# power_distribution.net
KiCad netlist of a schematic drawn in EAGLE
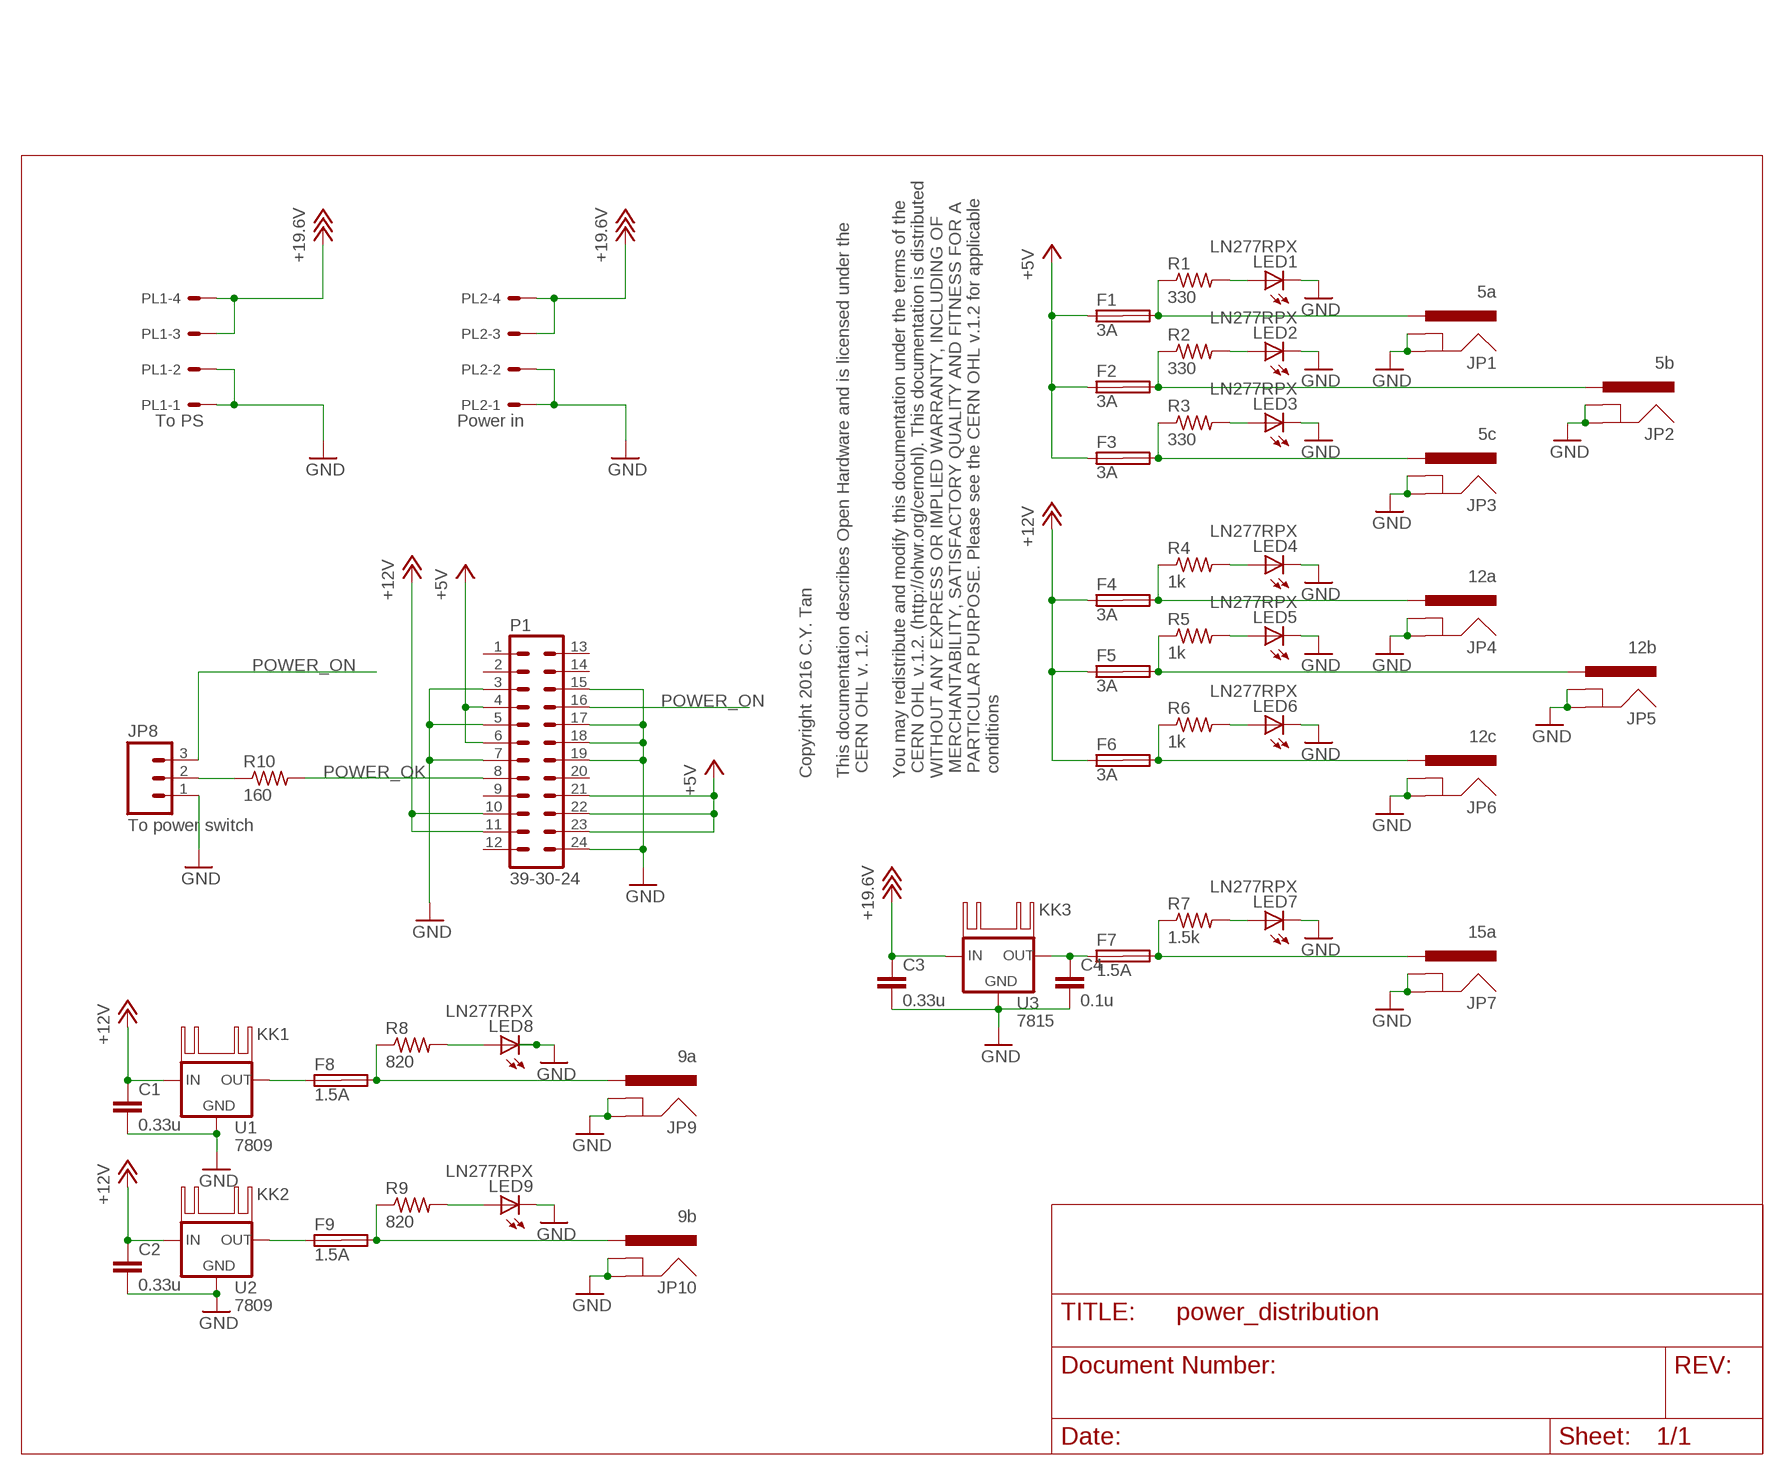
[diagram p0: schematic, sheet 1]

(export (version "E")
  (design (tool "Eeschema 10.0.6"))
  (components
    (comp (ref "C1")
      (value "0.33u")
      (footprint "eagle-import:CAP-PTH-5MM")
      (libsource (lib "eagle-import") (part "CAPPTH1"))
    )
    (comp (ref "C2")
      (value "0.33u")
      (footprint "eagle-import:CAP-PTH-5MM")
      (libsource (lib "eagle-import") (part "CAPPTH1"))
    )
    (comp (ref "C3")
      (value "0.33u")
      (footprint "eagle-import:CAP-PTH-5MM")
      (libsource (lib "eagle-import") (part "CAPPTH1"))
    )
    (comp (ref "C4")
      (value "0.1u")
      (footprint "eagle-import:CAP-PTH-5MM")
      (libsource (lib "eagle-import") (part "CAPPTH1"))
    )
    (comp (ref "F1")
      (value "3A")
      (footprint "eagle-import:SH32")
      (fields (field (name "MPN") "10207101009"))
      (libsource (lib "eagle-import") (part "SH32"))
    )
    (comp (ref "F2")
      (value "3A")
      (footprint "eagle-import:SH32")
      (fields (field (name "MPN") "10207101009"))
      (libsource (lib "eagle-import") (part "SH32"))
    )
    (comp (ref "F3")
      (value "3A")
      (footprint "eagle-import:SH32")
      (fields (field (name "MPN") "10207101009"))
      (libsource (lib "eagle-import") (part "SH32"))
    )
    (comp (ref "F4")
      (value "3A")
      (footprint "eagle-import:SH32")
      (fields (field (name "MPN") "10207101009"))
      (libsource (lib "eagle-import") (part "SH32"))
    )
    (comp (ref "F5")
      (value "3A")
      (footprint "eagle-import:SH32")
      (fields (field (name "MPN") "10207101009"))
      (libsource (lib "eagle-import") (part "SH32"))
    )
    (comp (ref "F6")
      (value "3A")
      (footprint "eagle-import:SH32")
      (fields (field (name "MPN") "10207101009"))
      (libsource (lib "eagle-import") (part "SH32"))
    )
    (comp (ref "F7")
      (value "1.5A")
      (footprint "eagle-import:SH32")
      (fields (field (name "MPN") "10207101009"))
      (libsource (lib "eagle-import") (part "SH32"))
    )
    (comp (ref "F8")
      (value "1.5A")
      (footprint "eagle-import:SH32")
      (fields (field (name "MPN") "10207101009"))
      (libsource (lib "eagle-import") (part "SH32"))
    )
    (comp (ref "F9")
      (value "1.5A")
      (footprint "eagle-import:SH32")
      (fields (field (name "MPN") "10207101009"))
      (libsource (lib "eagle-import") (part "SH32"))
    )
    (comp (ref "JP1")
      (value "5a")
      (footprint "eagle-import:POWER_JACK_V_PTH")
      (libsource (lib "eagle-import") (part "POWER_JACK"))
    )
    (comp (ref "JP2")
      (value "5b")
      (footprint "eagle-import:POWER_JACK_V_PTH")
      (libsource (lib "eagle-import") (part "POWER_JACK"))
    )
    (comp (ref "JP3")
      (value "5c")
      (footprint "eagle-import:POWER_JACK_V_PTH")
      (libsource (lib "eagle-import") (part "POWER_JACK"))
    )
    (comp (ref "JP4")
      (value "12a")
      (footprint "eagle-import:POWER_JACK_V_PTH")
      (libsource (lib "eagle-import") (part "POWER_JACK"))
    )
    (comp (ref "JP5")
      (value "12b")
      (footprint "eagle-import:POWER_JACK_V_PTH")
      (libsource (lib "eagle-import") (part "POWER_JACK"))
    )
    (comp (ref "JP6")
      (value "12c")
      (footprint "eagle-import:POWER_JACK_V_PTH")
      (libsource (lib "eagle-import") (part "POWER_JACK"))
    )
    (comp (ref "JP7")
      (value "15a")
      (footprint "eagle-import:POWER_JACK_V_PTH")
      (libsource (lib "eagle-import") (part "POWER_JACK"))
    )
    (comp (ref "JP8")
      (value "To power switch")
      (footprint "eagle-import:1X03")
      (libsource (lib "eagle-import") (part "M03PTH"))
    )
    (comp (ref "JP9")
      (value "9a")
      (footprint "eagle-import:POWER_JACK_V_PTH")
      (libsource (lib "eagle-import") (part "POWER_JACK"))
    )
    (comp (ref "JP10")
      (value "9b")
      (footprint "eagle-import:POWER_JACK_V_PTH")
      (libsource (lib "eagle-import") (part "POWER_JACK"))
    )
    (comp (ref "KK1")
      (value "TO-220_HEATSINK_4W")
      (footprint "eagle-import:TO-220-HEATSINK-4W")
      (libsource (lib "eagle-import") (part "TO-220_HEATSINK_4W"))
    )
    (comp (ref "KK2")
      (value "TO-220_HEATSINK_4W")
      (footprint "eagle-import:TO-220-HEATSINK-4W")
      (libsource (lib "eagle-import") (part "TO-220_HEATSINK_4W"))
    )
    (comp (ref "KK3")
      (value "TO-220_HEATSINK_4W")
      (footprint "eagle-import:TO-220-HEATSINK-4W")
      (libsource (lib "eagle-import") (part "TO-220_HEATSINK_4W"))
    )
    (comp (ref "LED1")
      (value "LN277RPX")
      (footprint "eagle-import:LED3MM")
      (libsource (lib "eagle-import") (part "LN277RPX"))
    )
    (comp (ref "LED2")
      (value "LN277RPX")
      (footprint "eagle-import:LED3MM")
      (libsource (lib "eagle-import") (part "LN277RPX"))
    )
    (comp (ref "LED3")
      (value "LN277RPX")
      (footprint "eagle-import:LED3MM")
      (libsource (lib "eagle-import") (part "LN277RPX"))
    )
    (comp (ref "LED4")
      (value "LN277RPX")
      (footprint "eagle-import:LED3MM")
      (libsource (lib "eagle-import") (part "LN277RPX"))
    )
    (comp (ref "LED5")
      (value "LN277RPX")
      (footprint "eagle-import:LED3MM")
      (libsource (lib "eagle-import") (part "LN277RPX"))
    )
    (comp (ref "LED6")
      (value "LN277RPX")
      (footprint "eagle-import:LED3MM")
      (libsource (lib "eagle-import") (part "LN277RPX"))
    )
    (comp (ref "LED7")
      (value "LN277RPX")
      (footprint "eagle-import:LED3MM")
      (libsource (lib "eagle-import") (part "LN277RPX"))
    )
    (comp (ref "LED8")
      (value "LN277RPX")
      (footprint "eagle-import:LED3MM")
      (libsource (lib "eagle-import") (part "LN277RPX"))
    )
    (comp (ref "LED9")
      (value "LN277RPX")
      (footprint "eagle-import:LED3MM")
      (libsource (lib "eagle-import") (part "LN277RPX"))
    )
    (comp (ref "P1")
      (value "39-30-24")
      (footprint "eagle-import:39-30-_24_")
      (libsource (lib "eagle-import") (part "39-30-?24?"))
    )
    (comp (ref "PL1")
      (value "To PS")
      (footprint "eagle-import:5569-4")
      (libsource (lib "eagle-import") (part "555X-4H"))
    )
    (comp (ref "PL2")
      (value "Power in")
      (footprint "eagle-import:5569-4")
      (libsource (lib "eagle-import") (part "555X-4H"))
    )
    (comp (ref "R1")
      (value "330")
      (footprint "eagle-import:0207_10")
      (libsource (lib "eagle-import") (part "R-US_0207/10"))
    )
    (comp (ref "R2")
      (value "330")
      (footprint "eagle-import:0207_10")
      (libsource (lib "eagle-import") (part "R-US_0207/10"))
    )
    (comp (ref "R3")
      (value "330")
      (footprint "eagle-import:0207_10")
      (libsource (lib "eagle-import") (part "R-US_0207/10"))
    )
    (comp (ref "R4")
      (value "1k")
      (footprint "eagle-import:0207_10")
      (libsource (lib "eagle-import") (part "R-US_0207/10"))
    )
    (comp (ref "R5")
      (value "1k")
      (footprint "eagle-import:0207_10")
      (libsource (lib "eagle-import") (part "R-US_0207/10"))
    )
    (comp (ref "R6")
      (value "1k")
      (footprint "eagle-import:0207_10")
      (libsource (lib "eagle-import") (part "R-US_0207/10"))
    )
    (comp (ref "R7")
      (value "1.5k")
      (footprint "eagle-import:0207_10")
      (libsource (lib "eagle-import") (part "R-US_0207/10"))
    )
    (comp (ref "R8")
      (value "820")
      (footprint "eagle-import:0207_10")
      (libsource (lib "eagle-import") (part "R-US_0207/10"))
    )
    (comp (ref "R9")
      (value "820")
      (footprint "eagle-import:0207_10")
      (libsource (lib "eagle-import") (part "R-US_0207/10"))
    )
    (comp (ref "R10")
      (value "160")
      (footprint "eagle-import:0207_10")
      (libsource (lib "eagle-import") (part "R-US_0207/10"))
    )
    (comp (ref "U1")
      (value "7809")
      (footprint "eagle-import:TO-220-ALT")
      (libsource (lib "eagle-import") (part "V_REG_78XX-TO-220"))
    )
    (comp (ref "U2")
      (value "7809")
      (footprint "eagle-import:TO-220-ALT")
      (libsource (lib "eagle-import") (part "V_REG_78XX-TO-220"))
    )
    (comp (ref "U3")
      (value "7815")
      (footprint "eagle-import:TO-220-ALT")
      (libsource (lib "eagle-import") (part "V_REG_78XX-TO-220"))
    )
  )
  (nets
    (net (code "1") (name "+5V") (class "Default")
      (node (ref "F1") (pin "1A") (pinfunction "1A_1A") (pintype "passive"))
      (node (ref "F2") (pin "1A") (pinfunction "1A_1A") (pintype "passive"))
      (node (ref "F3") (pin "1A") (pinfunction "1A_1A") (pintype "passive"))
      (node (ref "P1") (pin "21") (pinfunction "21_21") (pintype "passive"))
      (node (ref "P1") (pin "22") (pinfunction "22_22") (pintype "passive"))
      (node (ref "P1") (pin "23") (pinfunction "23_23") (pintype "passive"))
      (node (ref "P1") (pin "4") (pinfunction "4_4") (pintype "passive"))
      (node (ref "P1") (pin "6") (pinfunction "6_6") (pintype "passive"))
    )
    (net (code "2") (name "+12V") (class "Default")
      (node (ref "C1") (pin "1") (pinfunction "1_1") (pintype "passive"))
      (node (ref "C2") (pin "1") (pinfunction "1_1") (pintype "passive"))
      (node (ref "F4") (pin "1A") (pinfunction "1A_1A") (pintype "passive"))
      (node (ref "F5") (pin "1A") (pinfunction "1A_1A") (pintype "passive"))
      (node (ref "F6") (pin "1A") (pinfunction "1A_1A") (pintype "passive"))
      (node (ref "P1") (pin "10") (pinfunction "10_10") (pintype "passive"))
      (node (ref "P1") (pin "11") (pinfunction "11_11") (pintype "passive"))
      (node (ref "U1") (pin "IN") (pinfunction "IN_IN") (pintype "input"))
      (node (ref "U2") (pin "IN") (pinfunction "IN_IN") (pintype "input"))
    )
    (net (code "3") (name "+19.6V") (class "Default")
      (node (ref "C3") (pin "1") (pinfunction "1_1") (pintype "passive"))
      (node (ref "PL1") (pin "3") (pinfunction "S_3") (pintype "passive"))
      (node (ref "PL1") (pin "4") (pinfunction "S_4") (pintype "passive"))
      (node (ref "PL2") (pin "3") (pinfunction "S_3") (pintype "passive"))
      (node (ref "PL2") (pin "4") (pinfunction "S_4") (pintype "passive"))
      (node (ref "U3") (pin "IN") (pinfunction "IN_IN") (pintype "input"))
    )
    (net (code "4") (name "/POWER_OK") (class "Default")
      (node (ref "P1") (pin "8") (pinfunction "8_8") (pintype "passive"))
      (node (ref "R10") (pin "2") (pinfunction "2_2") (pintype "passive"))
    )
    (net (code "5") (name "/POWER_ON") (class "Default")
      (node (ref "JP8") (pin "3") (pinfunction "3_3") (pintype "passive"))
      (node (ref "P1") (pin "16") (pinfunction "16_16") (pintype "passive"))
    )
    (net (code "6") (name "GND") (class "Default")
      (node (ref "C1") (pin "2") (pinfunction "2_2") (pintype "passive"))
      (node (ref "C2") (pin "2") (pinfunction "2_2") (pintype "passive"))
      (node (ref "C3") (pin "2") (pinfunction "2_2") (pintype "passive"))
      (node (ref "C4") (pin "2") (pinfunction "2_2") (pintype "passive"))
      (node (ref "JP1") (pin "GND") (pinfunction "GND_GND") (pintype "bidirectional"))
      (node (ref "JP1") (pin "GNDBREAK") (pinfunction "GNDBREAK_GNDBREAK") (pintype "bidirectional"))
      (node (ref "JP10") (pin "GND") (pinfunction "GND_GND") (pintype "bidirectional"))
      (node (ref "JP10") (pin "GNDBREAK") (pinfunction "GNDBREAK_GNDBREAK") (pintype "bidirectional"))
      (node (ref "JP2") (pin "GND") (pinfunction "GND_GND") (pintype "bidirectional"))
      (node (ref "JP2") (pin "GNDBREAK") (pinfunction "GNDBREAK_GNDBREAK") (pintype "bidirectional"))
      (node (ref "JP3") (pin "GND") (pinfunction "GND_GND") (pintype "bidirectional"))
      (node (ref "JP3") (pin "GNDBREAK") (pinfunction "GNDBREAK_GNDBREAK") (pintype "bidirectional"))
      (node (ref "JP4") (pin "GND") (pinfunction "GND_GND") (pintype "bidirectional"))
      (node (ref "JP4") (pin "GNDBREAK") (pinfunction "GNDBREAK_GNDBREAK") (pintype "bidirectional"))
      (node (ref "JP5") (pin "GND") (pinfunction "GND_GND") (pintype "bidirectional"))
      (node (ref "JP5") (pin "GNDBREAK") (pinfunction "GNDBREAK_GNDBREAK") (pintype "bidirectional"))
      (node (ref "JP6") (pin "GND") (pinfunction "GND_GND") (pintype "bidirectional"))
      (node (ref "JP6") (pin "GNDBREAK") (pinfunction "GNDBREAK_GNDBREAK") (pintype "bidirectional"))
      (node (ref "JP7") (pin "GND") (pinfunction "GND_GND") (pintype "bidirectional"))
      (node (ref "JP7") (pin "GNDBREAK") (pinfunction "GNDBREAK_GNDBREAK") (pintype "bidirectional"))
      (node (ref "JP8") (pin "1") (pinfunction "1_1") (pintype "passive"))
      (node (ref "JP9") (pin "GND") (pinfunction "GND_GND") (pintype "bidirectional"))
      (node (ref "JP9") (pin "GNDBREAK") (pinfunction "GNDBREAK_GNDBREAK") (pintype "bidirectional"))
      (node (ref "LED1") (pin "K") (pinfunction "C_K") (pintype "passive"))
      (node (ref "LED2") (pin "K") (pinfunction "C_K") (pintype "passive"))
      (node (ref "LED3") (pin "K") (pinfunction "C_K") (pintype "passive"))
      (node (ref "LED4") (pin "K") (pinfunction "C_K") (pintype "passive"))
      (node (ref "LED5") (pin "K") (pinfunction "C_K") (pintype "passive"))
      (node (ref "LED6") (pin "K") (pinfunction "C_K") (pintype "passive"))
      (node (ref "LED7") (pin "K") (pinfunction "C_K") (pintype "passive"))
      (node (ref "LED8") (pin "K") (pinfunction "C_K") (pintype "passive"))
      (node (ref "LED9") (pin "K") (pinfunction "C_K") (pintype "passive"))
      (node (ref "P1") (pin "15") (pinfunction "15_15") (pintype "passive"))
      (node (ref "P1") (pin "17") (pinfunction "17_17") (pintype "passive"))
      (node (ref "P1") (pin "18") (pinfunction "18_18") (pintype "passive"))
      (node (ref "P1") (pin "19") (pinfunction "19_19") (pintype "passive"))
      (node (ref "P1") (pin "24") (pinfunction "24_24") (pintype "passive"))
      (node (ref "P1") (pin "3") (pinfunction "3_3") (pintype "passive"))
      (node (ref "P1") (pin "5") (pinfunction "5_5") (pintype "passive"))
      (node (ref "P1") (pin "7") (pinfunction "7_7") (pintype "passive"))
      (node (ref "PL1") (pin "1") (pinfunction "S_1") (pintype "passive"))
      (node (ref "PL1") (pin "2") (pinfunction "S_2") (pintype "passive"))
      (node (ref "PL2") (pin "1") (pinfunction "S_1") (pintype "passive"))
      (node (ref "PL2") (pin "2") (pinfunction "S_2") (pintype "passive"))
      (node (ref "U1") (pin "GND") (pinfunction "GND_GND") (pintype "input"))
      (node (ref "U2") (pin "GND") (pinfunction "GND_GND") (pintype "input"))
      (node (ref "U3") (pin "GND") (pinfunction "GND_GND") (pintype "input"))
    )
    (net (code "7") (name "Net-(C4-Pad1)") (class "Default")
      (node (ref "C4") (pin "1") (pinfunction "1_1") (pintype "passive"))
      (node (ref "F7") (pin "1A") (pinfunction "1A_1A") (pintype "passive"))
      (node (ref "U3") (pin "OUT") (pinfunction "OUT_OUT") (pintype "passive"))
    )
    (net (code "8") (name "Net-(F1-Pad2A)") (class "Default")
      (node (ref "F1") (pin "2A") (pinfunction "2A_2A") (pintype "passive"))
      (node (ref "JP1") (pin "PWR") (pinfunction "PWR_PWR") (pintype "bidirectional"))
      (node (ref "R1") (pin "1") (pinfunction "1_1") (pintype "passive"))
    )
    (net (code "9") (name "Net-(F2-Pad2A)") (class "Default")
      (node (ref "F2") (pin "2A") (pinfunction "2A_2A") (pintype "passive"))
      (node (ref "JP2") (pin "PWR") (pinfunction "PWR_PWR") (pintype "bidirectional"))
      (node (ref "R2") (pin "1") (pinfunction "1_1") (pintype "passive"))
    )
    (net (code "10") (name "Net-(F3-Pad2A)") (class "Default")
      (node (ref "F3") (pin "2A") (pinfunction "2A_2A") (pintype "passive"))
      (node (ref "JP3") (pin "PWR") (pinfunction "PWR_PWR") (pintype "bidirectional"))
      (node (ref "R3") (pin "1") (pinfunction "1_1") (pintype "passive"))
    )
    (net (code "11") (name "Net-(F4-Pad2A)") (class "Default")
      (node (ref "F4") (pin "2A") (pinfunction "2A_2A") (pintype "passive"))
      (node (ref "JP4") (pin "PWR") (pinfunction "PWR_PWR") (pintype "bidirectional"))
      (node (ref "R4") (pin "1") (pinfunction "1_1") (pintype "passive"))
    )
    (net (code "12") (name "Net-(F5-Pad2A)") (class "Default")
      (node (ref "F5") (pin "2A") (pinfunction "2A_2A") (pintype "passive"))
      (node (ref "JP5") (pin "PWR") (pinfunction "PWR_PWR") (pintype "bidirectional"))
      (node (ref "R5") (pin "1") (pinfunction "1_1") (pintype "passive"))
    )
    (net (code "13") (name "Net-(F6-Pad2A)") (class "Default")
      (node (ref "F6") (pin "2A") (pinfunction "2A_2A") (pintype "passive"))
      (node (ref "JP6") (pin "PWR") (pinfunction "PWR_PWR") (pintype "bidirectional"))
      (node (ref "R6") (pin "1") (pinfunction "1_1") (pintype "passive"))
    )
    (net (code "14") (name "Net-(F7-Pad2A)") (class "Default")
      (node (ref "F7") (pin "2A") (pinfunction "2A_2A") (pintype "passive"))
      (node (ref "JP7") (pin "PWR") (pinfunction "PWR_PWR") (pintype "bidirectional"))
      (node (ref "R7") (pin "1") (pinfunction "1_1") (pintype "passive"))
    )
    (net (code "15") (name "Net-(F8-Pad1A)") (class "Default")
      (node (ref "F8") (pin "1A") (pinfunction "1A_1A") (pintype "passive"))
      (node (ref "U1") (pin "OUT") (pinfunction "OUT_OUT") (pintype "passive"))
    )
    (net (code "16") (name "Net-(F8-Pad2A)") (class "Default")
      (node (ref "F8") (pin "2A") (pinfunction "2A_2A") (pintype "passive"))
      (node (ref "JP9") (pin "PWR") (pinfunction "PWR_PWR") (pintype "bidirectional"))
      (node (ref "R8") (pin "1") (pinfunction "1_1") (pintype "passive"))
    )
    (net (code "17") (name "Net-(F9-Pad1A)") (class "Default")
      (node (ref "F9") (pin "1A") (pinfunction "1A_1A") (pintype "passive"))
      (node (ref "U2") (pin "OUT") (pinfunction "OUT_OUT") (pintype "passive"))
    )
    (net (code "18") (name "Net-(F9-Pad2A)") (class "Default")
      (node (ref "F9") (pin "2A") (pinfunction "2A_2A") (pintype "passive"))
      (node (ref "JP10") (pin "PWR") (pinfunction "PWR_PWR") (pintype "bidirectional"))
      (node (ref "R9") (pin "1") (pinfunction "1_1") (pintype "passive"))
    )
    (net (code "19") (name "Net-(JP8-Pad2)") (class "Default")
      (node (ref "JP8") (pin "2") (pinfunction "2_2") (pintype "passive"))
      (node (ref "R10") (pin "1") (pinfunction "1_1") (pintype "passive"))
    )
    (net (code "20") (name "Net-(LED1-PadA)") (class "Default")
      (node (ref "LED1") (pin "A") (pinfunction "A_A") (pintype "passive"))
      (node (ref "R1") (pin "2") (pinfunction "2_2") (pintype "passive"))
    )
    (net (code "21") (name "Net-(LED2-PadA)") (class "Default")
      (node (ref "LED2") (pin "A") (pinfunction "A_A") (pintype "passive"))
      (node (ref "R2") (pin "2") (pinfunction "2_2") (pintype "passive"))
    )
    (net (code "22") (name "Net-(LED3-PadA)") (class "Default")
      (node (ref "LED3") (pin "A") (pinfunction "A_A") (pintype "passive"))
      (node (ref "R3") (pin "2") (pinfunction "2_2") (pintype "passive"))
    )
    (net (code "23") (name "Net-(LED4-PadA)") (class "Default")
      (node (ref "LED4") (pin "A") (pinfunction "A_A") (pintype "passive"))
      (node (ref "R4") (pin "2") (pinfunction "2_2") (pintype "passive"))
    )
    (net (code "24") (name "Net-(LED5-PadA)") (class "Default")
      (node (ref "LED5") (pin "A") (pinfunction "A_A") (pintype "passive"))
      (node (ref "R5") (pin "2") (pinfunction "2_2") (pintype "passive"))
    )
    (net (code "25") (name "Net-(LED6-PadA)") (class "Default")
      (node (ref "LED6") (pin "A") (pinfunction "A_A") (pintype "passive"))
      (node (ref "R6") (pin "2") (pinfunction "2_2") (pintype "passive"))
    )
    (net (code "26") (name "Net-(LED7-PadA)") (class "Default")
      (node (ref "LED7") (pin "A") (pinfunction "A_A") (pintype "passive"))
      (node (ref "R7") (pin "2") (pinfunction "2_2") (pintype "passive"))
    )
    (net (code "27") (name "Net-(LED8-PadA)") (class "Default")
      (node (ref "LED8") (pin "A") (pinfunction "A_A") (pintype "passive"))
      (node (ref "R8") (pin "2") (pinfunction "2_2") (pintype "passive"))
    )
    (net (code "28") (name "Net-(LED9-PadA)") (class "Default")
      (node (ref "LED9") (pin "A") (pinfunction "A_A") (pintype "passive"))
      (node (ref "R9") (pin "2") (pinfunction "2_2") (pintype "passive"))
    )
    (net (code "29") (name "unconnected-(F1-Pad1B)") (class "Default")
      (node (ref "F1") (pin "1B") (pinfunction "1B_1B") (pintype "passive"))
    )
    (net (code "30") (name "unconnected-(F1-Pad2B)") (class "Default")
      (node (ref "F1") (pin "2B") (pinfunction "2B_2B") (pintype "passive"))
    )
    (net (code "31") (name "unconnected-(F2-Pad1B)") (class "Default")
      (node (ref "F2") (pin "1B") (pinfunction "1B_1B") (pintype "passive"))
    )
    (net (code "32") (name "unconnected-(F2-Pad2B)") (class "Default")
      (node (ref "F2") (pin "2B") (pinfunction "2B_2B") (pintype "passive"))
    )
    (net (code "33") (name "unconnected-(F3-Pad1B)") (class "Default")
      (node (ref "F3") (pin "1B") (pinfunction "1B_1B") (pintype "passive"))
    )
    (net (code "34") (name "unconnected-(F3-Pad2B)") (class "Default")
      (node (ref "F3") (pin "2B") (pinfunction "2B_2B") (pintype "passive"))
    )
    (net (code "35") (name "unconnected-(F4-Pad1B)") (class "Default")
      (node (ref "F4") (pin "1B") (pinfunction "1B_1B") (pintype "passive"))
    )
    (net (code "36") (name "unconnected-(F4-Pad2B)") (class "Default")
      (node (ref "F4") (pin "2B") (pinfunction "2B_2B") (pintype "passive"))
    )
    (net (code "37") (name "unconnected-(F5-Pad1B)") (class "Default")
      (node (ref "F5") (pin "1B") (pinfunction "1B_1B") (pintype "passive"))
    )
    (net (code "38") (name "unconnected-(F5-Pad2B)") (class "Default")
      (node (ref "F5") (pin "2B") (pinfunction "2B_2B") (pintype "passive"))
    )
    (net (code "39") (name "unconnected-(F6-Pad1B)") (class "Default")
      (node (ref "F6") (pin "1B") (pinfunction "1B_1B") (pintype "passive"))
    )
    (net (code "40") (name "unconnected-(F6-Pad2B)") (class "Default")
      (node (ref "F6") (pin "2B") (pinfunction "2B_2B") (pintype "passive"))
    )
    (net (code "41") (name "unconnected-(F7-Pad1B)") (class "Default")
      (node (ref "F7") (pin "1B") (pinfunction "1B_1B") (pintype "passive"))
    )
    (net (code "42") (name "unconnected-(F7-Pad2B)") (class "Default")
      (node (ref "F7") (pin "2B") (pinfunction "2B_2B") (pintype "passive"))
    )
    (net (code "43") (name "unconnected-(F8-Pad1B)") (class "Default")
      (node (ref "F8") (pin "1B") (pinfunction "1B_1B") (pintype "passive"))
    )
    (net (code "44") (name "unconnected-(F8-Pad2B)") (class "Default")
      (node (ref "F8") (pin "2B") (pinfunction "2B_2B") (pintype "passive"))
    )
    (net (code "45") (name "unconnected-(F9-Pad1B)") (class "Default")
      (node (ref "F9") (pin "1B") (pinfunction "1B_1B") (pintype "passive"))
    )
    (net (code "46") (name "unconnected-(F9-Pad2B)") (class "Default")
      (node (ref "F9") (pin "2B") (pinfunction "2B_2B") (pintype "passive"))
    )
    (net (code "47") (name "unconnected-(P1-Pad1)") (class "Default")
      (node (ref "P1") (pin "1") (pinfunction "1_1") (pintype "passive"))
    )
    (net (code "48") (name "unconnected-(P1-Pad2)") (class "Default")
      (node (ref "P1") (pin "2") (pinfunction "2_2") (pintype "passive"))
    )
    (net (code "49") (name "unconnected-(P1-Pad9)") (class "Default")
      (node (ref "P1") (pin "9") (pinfunction "9_9") (pintype "passive"))
    )
    (net (code "50") (name "unconnected-(P1-Pad12)") (class "Default")
      (node (ref "P1") (pin "12") (pinfunction "12_12") (pintype "passive"))
    )
    (net (code "51") (name "unconnected-(P1-Pad13)") (class "Default")
      (node (ref "P1") (pin "13") (pinfunction "13_13") (pintype "passive"))
    )
    (net (code "52") (name "unconnected-(P1-Pad14)") (class "Default")
      (node (ref "P1") (pin "14") (pinfunction "14_14") (pintype "passive"))
    )
    (net (code "53") (name "unconnected-(P1-Pad20)") (class "Default")
      (node (ref "P1") (pin "20") (pinfunction "20_20") (pintype "passive"))
    )
  )
)
